# HB-UNI-SEN-CAP-MOIST_V1_2.net
KiCad netlist of a schematic drawn in EAGLE
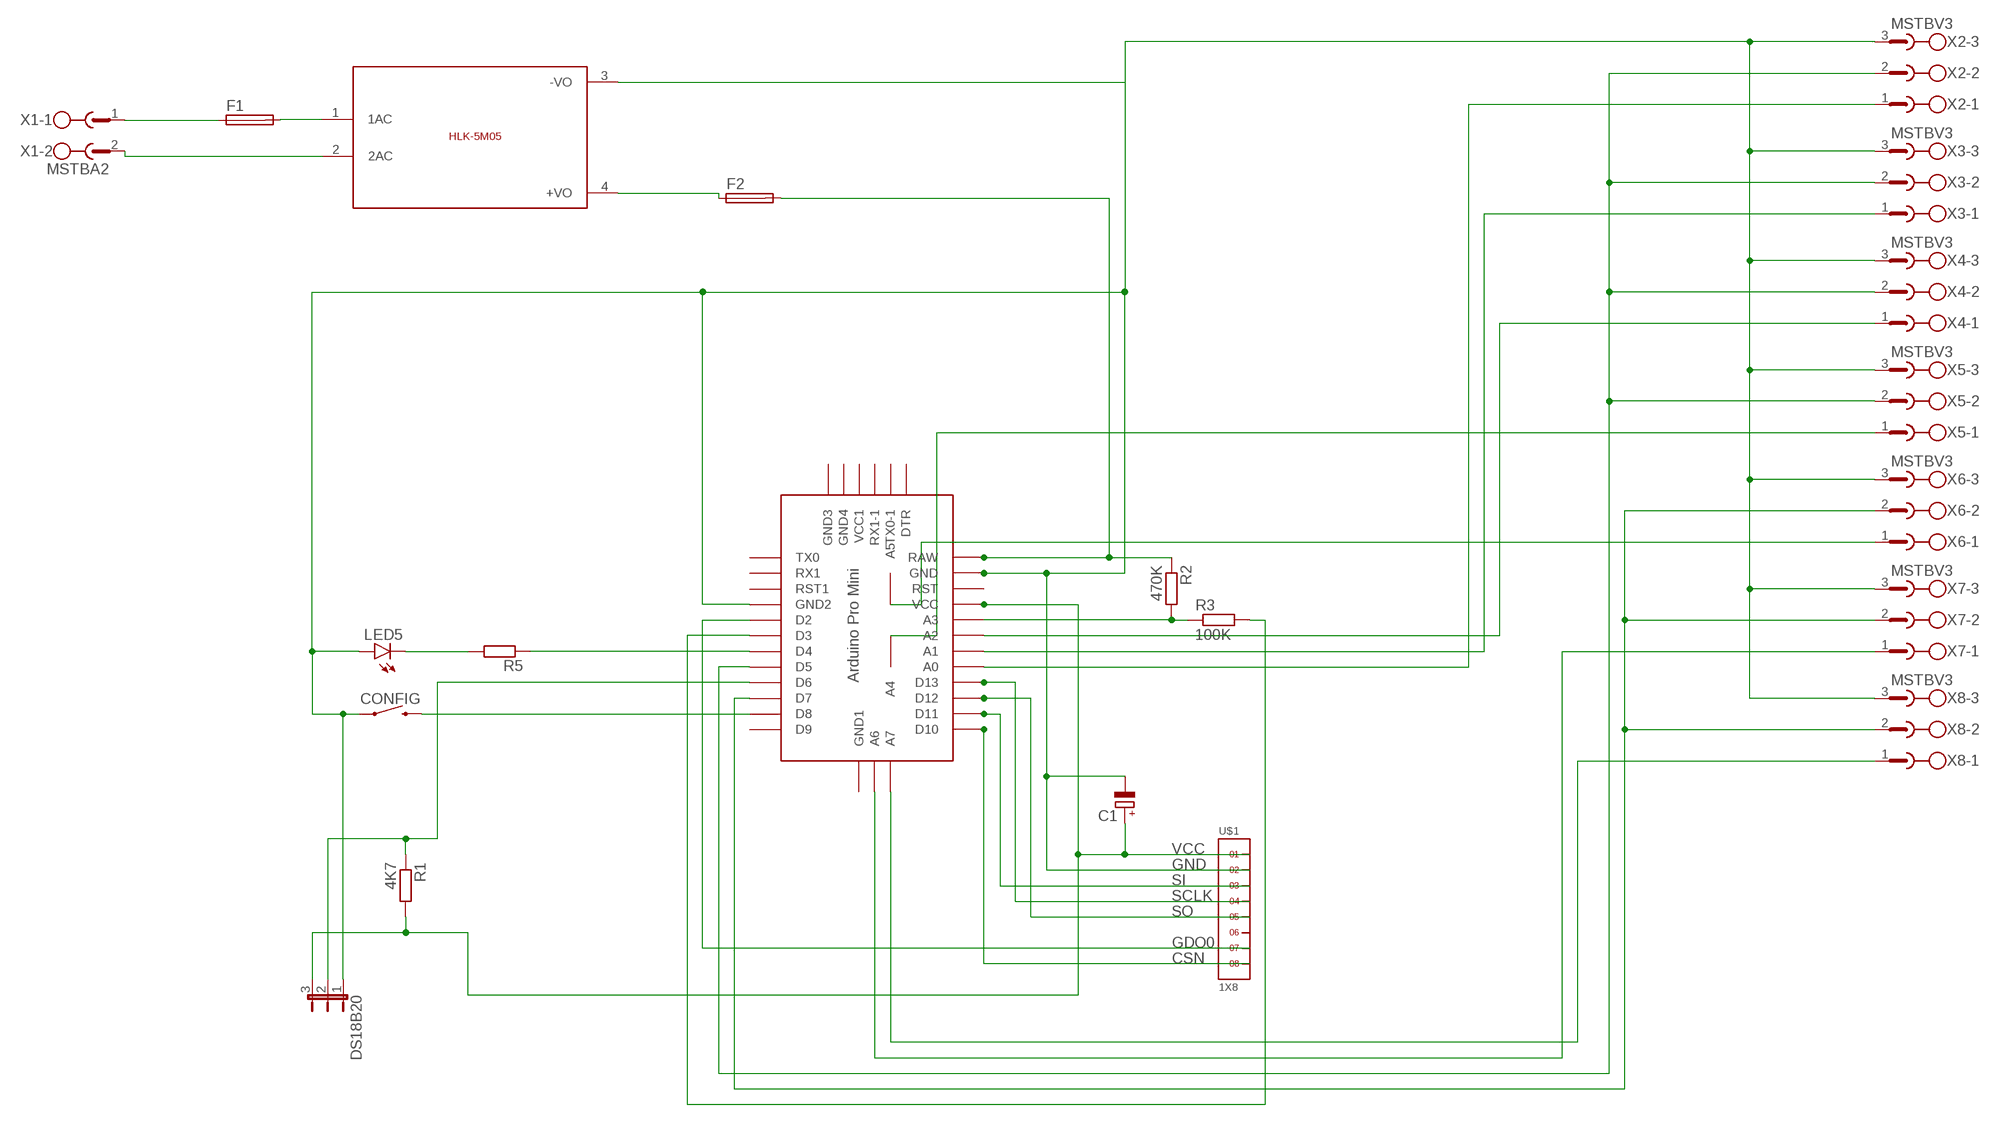
[diagram p0: schematic, sheet 1]

(export (version "E")
  (design (tool "Eeschema 10.0.6"))
  (components
    (comp (ref "C1")
      (value "CPOL-EUE2.5-5")
      (footprint "eagle-import:E2,5-5")
      (libsource (lib "eagle-import") (part "CPOL-EUE2.5-5"))
    )
    (comp (ref "CONFIG")
      (value "MOMENTARY-SWITCH-SPST-PTH-6.0MM-KIT")
      (footprint "eagle-import:TACTILE_SWITCH_PTH_6.0MM_KIT")
      (libsource (lib "eagle-import") (part "MOMENTARY-SWITCH-SPST-PTH-6.0MM-KIT"))
    )
    (comp (ref "DS18B20")
      (value "JP2E")
      (footprint "eagle-import:JP2")
      (libsource (lib "eagle-import") (part "JP2E"))
    )
    (comp (ref "F1")
      (value "SH22,5A")
      (footprint "eagle-import:SH22,5A")
      (fields (field (name "MPN") "0031.7701.11"))
      (libsource (lib "eagle-import") (part "SH22,5A"))
    )
    (comp (ref "F2")
      (value "SH22,5A")
      (footprint "eagle-import:SH22,5A")
      (fields (field (name "MPN") "0031.7701.11"))
      (libsource (lib "eagle-import") (part "SH22,5A"))
    )
    (comp (ref "LED5")
      (value "LED3MM")
      (footprint "eagle-import:LED3MM")
      (libsource (lib "eagle-import") (part "LED3MM"))
    )
    (comp (ref "R1")
      (value "4K7")
      (footprint "eagle-import:0309_10")
      (libsource (lib "eagle-import") (part "R-EU_0309/10"))
    )
    (comp (ref "R2")
      (value "470K")
      (footprint "eagle-import:0309_10")
      (libsource (lib "eagle-import") (part "R-EU_0309/10"))
    )
    (comp (ref "R3")
      (value "100K")
      (footprint "eagle-import:0309_10")
      (libsource (lib "eagle-import") (part "R-EU_0309/10"))
    )
    (comp (ref "R5")
      (value "R-EU_0309/10")
      (footprint "eagle-import:0309_10")
      (libsource (lib "eagle-import") (part "R-EU_0309/10"))
    )
    (comp (ref "U$1")
      (value "1X8")
      (footprint "eagle-import:1X8")
      (libsource (lib "eagle-import") (part "1X8"))
    )
    (comp (ref "U$2")
      (value "ABK-PRO-MINI")
      (footprint "eagle-import:ABK-PRO-MINI")
      (libsource (lib "eagle-import") (part "ABK-PRO-MINI"))
    )
    (comp (ref "U$3")
      (value "5VDC/5W")
      (footprint "eagle-import:HLK-5M05")
      (libsource (lib "eagle-import") (part "HLK-5M05"))
    )
    (comp (ref "X1")
      (value "MSTBA2")
      (footprint "eagle-import:MSTBA2")
      (fields (field (name "MF") "FARNELL") (field (name "MPN") "1757242"))
      (libsource (lib "eagle-import") (part "MSTBA2"))
    )
    (comp (ref "X2")
      (value "MSTBV3")
      (footprint "eagle-import:MSTBV3")
      (fields (field (name "MPN") "MSTBV 2,5/3-GF-5.08"))
      (libsource (lib "eagle-import") (part "MSTBV3"))
    )
    (comp (ref "X3")
      (value "MSTBV3")
      (footprint "eagle-import:MSTBV3")
      (fields (field (name "MPN") "MSTBV 2,5/3-GF-5.08"))
      (libsource (lib "eagle-import") (part "MSTBV3"))
    )
    (comp (ref "X4")
      (value "MSTBV3")
      (footprint "eagle-import:MSTBV3")
      (fields (field (name "MPN") "MSTBV 2,5/3-GF-5.08"))
      (libsource (lib "eagle-import") (part "MSTBV3"))
    )
    (comp (ref "X5")
      (value "MSTBV3")
      (footprint "eagle-import:MSTBV3")
      (fields (field (name "MPN") "MSTBV 2,5/3-GF-5.08"))
      (libsource (lib "eagle-import") (part "MSTBV3"))
    )
    (comp (ref "X6")
      (value "MSTBV3")
      (footprint "eagle-import:MSTBV3")
      (fields (field (name "MPN") "MSTBV 2,5/3-GF-5.08"))
      (libsource (lib "eagle-import") (part "MSTBV3"))
    )
    (comp (ref "X7")
      (value "MSTBV3")
      (footprint "eagle-import:MSTBV3")
      (fields (field (name "MPN") "MSTBV 2,5/3-GF-5.08"))
      (libsource (lib "eagle-import") (part "MSTBV3"))
    )
    (comp (ref "X8")
      (value "MSTBV3")
      (footprint "eagle-import:MSTBV3")
      (fields (field (name "MPN") "MSTBV 2,5/3-GF-5.08"))
      (libsource (lib "eagle-import") (part "MSTBV3"))
    )
  )
  (nets
    (net (code "1") (name "/CSN") (class "Default")
      (node (ref "U$1") (pin "8") (pinfunction "8_8") (pintype "bidirectional"))
      (node (ref "U$2") (pin "D10") (pinfunction "D10_D10") (pintype "bidirectional"))
    )
    (net (code "2") (name "/GDO0") (class "Default")
      (node (ref "U$1") (pin "7") (pinfunction "7_7") (pintype "bidirectional"))
      (node (ref "U$2") (pin "D2") (pinfunction "D2_D2") (pintype "bidirectional"))
    )
    (net (code "3") (name "/GND") (class "Default")
      (node (ref "C1") (pin "-") (pinfunction "-_-") (pintype "passive"))
      (node (ref "CONFIG") (pin "1") (pinfunction "1_1") (pintype "passive"))
      (node (ref "DS18B20") (pin "1") (pinfunction "1_1") (pintype "passive"))
      (node (ref "LED5") (pin "A") (pinfunction "A_A") (pintype "passive"))
      (node (ref "U$1") (pin "2") (pinfunction "2_2") (pintype "bidirectional"))
      (node (ref "U$2") (pin "GND") (pinfunction "GND_GND") (pintype "bidirectional"))
      (node (ref "U$2") (pin "GND1") (pinfunction "GND2_GND1") (pintype "bidirectional"))
      (node (ref "U$3") (pin "3") (pinfunction "-VO_3") (pintype "bidirectional"))
      (node (ref "X2") (pin "3") (pinfunction "1_3") (pintype "passive"))
      (node (ref "X3") (pin "3") (pinfunction "1_3") (pintype "passive"))
      (node (ref "X4") (pin "3") (pinfunction "1_3") (pintype "passive"))
      (node (ref "X5") (pin "3") (pinfunction "1_3") (pintype "passive"))
      (node (ref "X6") (pin "3") (pinfunction "1_3") (pintype "passive"))
      (node (ref "X7") (pin "3") (pinfunction "1_3") (pintype "passive"))
      (node (ref "X8") (pin "3") (pinfunction "1_3") (pintype "passive"))
    )
    (net (code "4") (name "/SCLK") (class "Default")
      (node (ref "U$1") (pin "4") (pinfunction "4_4") (pintype "bidirectional"))
      (node (ref "U$2") (pin "D13") (pinfunction "D13_D13") (pintype "bidirectional"))
    )
    (net (code "5") (name "/SI") (class "Default")
      (node (ref "U$1") (pin "3") (pinfunction "3_3") (pintype "bidirectional"))
      (node (ref "U$2") (pin "D11") (pinfunction "D11_D11") (pintype "bidirectional"))
    )
    (net (code "6") (name "/SO") (class "Default")
      (node (ref "U$1") (pin "5") (pinfunction "5_5") (pintype "bidirectional"))
      (node (ref "U$2") (pin "D12") (pinfunction "D12_D12") (pintype "bidirectional"))
    )
    (net (code "7") (name "/VCC") (class "Default")
      (node (ref "C1") (pin "+") (pinfunction "+_+") (pintype "passive"))
      (node (ref "DS18B20") (pin "3") (pinfunction "3_3") (pintype "passive"))
      (node (ref "R1") (pin "2") (pinfunction "2_2") (pintype "passive"))
      (node (ref "U$1") (pin "1") (pinfunction "1_1") (pintype "bidirectional"))
      (node (ref "U$2") (pin "VCC") (pinfunction "VCC_VCC") (pintype "bidirectional"))
    )
    (net (code "8") (name "Net-(CONFIG-2)") (class "Default")
      (node (ref "CONFIG") (pin "3") (pinfunction "2_3") (pintype "passive"))
      (node (ref "U$2") (pin "D8") (pinfunction "D8_D8") (pintype "bidirectional"))
    )
    (net (code "9") (name "Net-(DS18B20-Pad2)") (class "Default")
      (node (ref "DS18B20") (pin "2") (pinfunction "2_2") (pintype "passive"))
      (node (ref "R1") (pin "1") (pinfunction "1_1") (pintype "passive"))
      (node (ref "U$2") (pin "D6") (pinfunction "D6_D6") (pintype "bidirectional"))
    )
    (net (code "10") (name "Net-(F1-Pad1)") (class "Default")
      (node (ref "F1") (pin "1") (pinfunction "1_1") (pintype "passive"))
      (node (ref "X1") (pin "1") (pinfunction "1_1") (pintype "passive"))
    )
    (net (code "11") (name "Net-(F2-Pad2)") (class "Default")
      (node (ref "F2") (pin "2") (pinfunction "2_2") (pintype "passive"))
      (node (ref "R2") (pin "1") (pinfunction "1_1") (pintype "passive"))
      (node (ref "U$2") (pin "RAW") (pinfunction "RAW_RAW") (pintype "bidirectional"))
    )
    (net (code "12") (name "Net-(LED5-C)") (class "Default")
      (node (ref "LED5") (pin "K") (pinfunction "C_K") (pintype "passive"))
      (node (ref "R5") (pin "2") (pinfunction "2_2") (pintype "passive"))
    )
    (net (code "13") (name "Net-(R2-Pad2)") (class "Default")
      (node (ref "R2") (pin "2") (pinfunction "2_2") (pintype "passive"))
      (node (ref "R3") (pin "1") (pinfunction "1_1") (pintype "passive"))
      (node (ref "U$2") (pin "A3") (pinfunction "A3_A3") (pintype "bidirectional"))
    )
    (net (code "14") (name "Net-(R3-Pad2)") (class "Default")
      (node (ref "R3") (pin "2") (pinfunction "2_2") (pintype "passive"))
      (node (ref "U$2") (pin "D3") (pinfunction "D3_D3") (pintype "bidirectional"))
    )
    (net (code "15") (name "Net-(R5-Pad1)") (class "Default")
      (node (ref "R5") (pin "1") (pinfunction "1_1") (pintype "passive"))
      (node (ref "U$2") (pin "D4") (pinfunction "D4_D4") (pintype "bidirectional"))
    )
    (net (code "16") (name "Net-(U$2-PadA0)") (class "Default")
      (node (ref "U$2") (pin "A0") (pinfunction "A0_A0") (pintype "bidirectional"))
      (node (ref "X2") (pin "1") (pinfunction "1_1") (pintype "passive"))
    )
    (net (code "17") (name "Net-(U$2-PadA1)") (class "Default")
      (node (ref "U$2") (pin "A1") (pinfunction "A1_A1") (pintype "bidirectional"))
      (node (ref "X3") (pin "1") (pinfunction "1_1") (pintype "passive"))
    )
    (net (code "18") (name "Net-(U$2-PadA2)") (class "Default")
      (node (ref "U$2") (pin "A2") (pinfunction "A2_A2") (pintype "bidirectional"))
      (node (ref "X4") (pin "1") (pinfunction "1_1") (pintype "passive"))
    )
    (net (code "19") (name "Net-(U$2-PadA4)") (class "Default")
      (node (ref "U$2") (pin "A4") (pinfunction "A4_A4") (pintype "bidirectional"))
      (node (ref "X5") (pin "1") (pinfunction "1_1") (pintype "passive"))
    )
    (net (code "20") (name "Net-(U$2-PadA5)") (class "Default")
      (node (ref "U$2") (pin "A5") (pinfunction "A5_A5") (pintype "bidirectional"))
      (node (ref "X6") (pin "1") (pinfunction "1_1") (pintype "passive"))
    )
    (net (code "21") (name "Net-(U$2-PadA6)") (class "Default")
      (node (ref "U$2") (pin "A6") (pinfunction "A6_A6") (pintype "bidirectional"))
      (node (ref "X7") (pin "1") (pinfunction "1_1") (pintype "passive"))
    )
    (net (code "22") (name "Net-(U$2-PadA7)") (class "Default")
      (node (ref "U$2") (pin "A7") (pinfunction "A7_A7") (pintype "bidirectional"))
      (node (ref "X8") (pin "1") (pinfunction "1_1") (pintype "passive"))
    )
    (net (code "23") (name "Net-(U$3-+VO)") (class "Default")
      (node (ref "F2") (pin "1") (pinfunction "1_1") (pintype "passive"))
      (node (ref "U$3") (pin "4") (pinfunction "+VO_4") (pintype "bidirectional"))
    )
    (net (code "24") (name "Net-(U$3-1AC)") (class "Default")
      (node (ref "F1") (pin "2") (pinfunction "2_2") (pintype "passive"))
      (node (ref "U$3") (pin "1") (pinfunction "1AC_1") (pintype "bidirectional"))
    )
    (net (code "25") (name "Net-(U$3-2AC)") (class "Default")
      (node (ref "U$3") (pin "2") (pinfunction "2AC_2") (pintype "bidirectional"))
      (node (ref "X1") (pin "2") (pinfunction "1_2") (pintype "passive"))
    )
    (net (code "26") (name "Net-(X2B-1)") (class "Default")
      (node (ref "U$2") (pin "D5") (pinfunction "D5_D5") (pintype "bidirectional"))
      (node (ref "X2") (pin "2") (pinfunction "1_2") (pintype "passive"))
      (node (ref "X3") (pin "2") (pinfunction "1_2") (pintype "passive"))
      (node (ref "X4") (pin "2") (pinfunction "1_2") (pintype "passive"))
      (node (ref "X5") (pin "2") (pinfunction "1_2") (pintype "passive"))
    )
    (net (code "27") (name "Net-(X6B-1)") (class "Default")
      (node (ref "U$2") (pin "D7") (pinfunction "D7_D7") (pintype "bidirectional"))
      (node (ref "X6") (pin "2") (pinfunction "1_2") (pintype "passive"))
      (node (ref "X7") (pin "2") (pinfunction "1_2") (pintype "passive"))
      (node (ref "X8") (pin "2") (pinfunction "1_2") (pintype "passive"))
    )
    (net (code "28") (name "unconnected-(U$1-Pad6)") (class "Default")
      (node (ref "U$1") (pin "6") (pinfunction "6_6") (pintype "bidirectional"))
    )
    (net (code "29") (name "unconnected-(U$2-GND1-PadGND4)") (class "Default")
      (node (ref "U$2") (pin "GND4") (pinfunction "GND1_GND4") (pintype "bidirectional"))
    )
    (net (code "30") (name "unconnected-(U$2-GND3-PadGND2)") (class "Default")
      (node (ref "U$2") (pin "GND2") (pinfunction "GND3_GND2") (pintype "bidirectional"))
    )
    (net (code "31") (name "unconnected-(U$2-GND4-PadGND3)") (class "Default")
      (node (ref "U$2") (pin "GND3") (pinfunction "GND4_GND3") (pintype "bidirectional"))
    )
    (net (code "32") (name "unconnected-(U$2-PadD9)") (class "Default")
      (node (ref "U$2") (pin "D9") (pinfunction "D9_D9") (pintype "bidirectional"))
    )
    (net (code "33") (name "unconnected-(U$2-PadDTR)") (class "Default")
      (node (ref "U$2") (pin "DTR") (pinfunction "DTR_DTR") (pintype "bidirectional"))
    )
    (net (code "34") (name "unconnected-(U$2-PadRST)") (class "Default")
      (node (ref "U$2") (pin "RST") (pinfunction "RST_RST") (pintype "bidirectional"))
    )
    (net (code "35") (name "unconnected-(U$2-PadRST1)") (class "Default")
      (node (ref "U$2") (pin "RST1") (pinfunction "RST1_RST1") (pintype "bidirectional"))
    )
    (net (code "36") (name "unconnected-(U$2-PadRX1)") (class "Default")
      (node (ref "U$2") (pin "RX1") (pinfunction "RX1_RX1") (pintype "bidirectional"))
    )
    (net (code "37") (name "unconnected-(U$2-PadRX1-1)") (class "Default")
      (node (ref "U$2") (pin "RX1-1") (pinfunction "RX1-1_RX1-1") (pintype "bidirectional"))
    )
    (net (code "38") (name "unconnected-(U$2-PadTX0)") (class "Default")
      (node (ref "U$2") (pin "TX0") (pinfunction "TX0_TX0") (pintype "bidirectional"))
    )
    (net (code "39") (name "unconnected-(U$2-PadTX0-1)") (class "Default")
      (node (ref "U$2") (pin "TX0-1") (pinfunction "TX0-1_TX0-1") (pintype "bidirectional"))
    )
    (net (code "40") (name "unconnected-(U$2-PadVCC1)") (class "Default")
      (node (ref "U$2") (pin "VCC1") (pinfunction "VCC1_VCC1") (pintype "bidirectional"))
    )
  )
)
